# 7SEG_ClockLed.net
KiCad netlist of a schematic drawn in Altium Designer
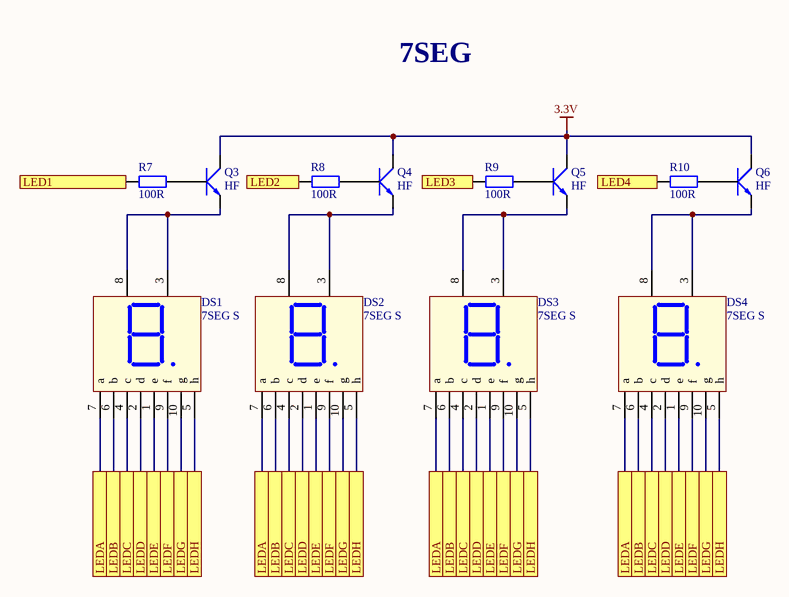
[diagram p0: 7SEG_ClockLed.SchDoc]

(export (version "E")
  (design (tool "Eeschema 10.0.6"))
  (components
    (comp (ref "DS1")
      (value "7SEG S")
      (footprint "7SEGS")
      (description "Single 7 Seg Dipslay")
      (libsource (lib "syhaunguyen") (part "LED7S"))
    )
    (comp (ref "DS2")
      (value "7SEG S")
      (footprint "7SEGS")
      (description "Single 7 Seg Dipslay")
      (libsource (lib "syhaunguyen") (part "LED7S"))
    )
    (comp (ref "DS3")
      (value "7SEG S")
      (footprint "7SEGS")
      (description "Single 7 Seg Dipslay")
      (libsource (lib "syhaunguyen") (part "LED7S"))
    )
    (comp (ref "DS4")
      (value "7SEG S")
      (footprint "7SEGS")
      (description "Single 7 Seg Dipslay")
      (libsource (lib "syhaunguyen") (part "LED7S"))
    )
    (comp (ref "Q3")
      (value "HF")
      (footprint "SOT23")
      (description "NPN transistor")
      (libsource (lib "Altium_Lib_by_KhueNguyenCreator") (part "C1815 HF SMD"))
    )
    (comp (ref "Q4")
      (value "HF")
      (footprint "SOT23")
      (description "NPN transistor")
      (libsource (lib "Altium_Lib_by_KhueNguyenCreator") (part "C1815 HF SMD"))
    )
    (comp (ref "Q5")
      (value "HF")
      (footprint "SOT23")
      (description "NPN transistor")
      (libsource (lib "Altium_Lib_by_KhueNguyenCreator") (part "C1815 HF SMD"))
    )
    (comp (ref "Q6")
      (value "HF")
      (footprint "SOT23")
      (description "NPN transistor")
      (libsource (lib "Altium_Lib_by_KhueNguyenCreator") (part "C1815 HF SMD"))
    )
    (comp (ref "R7")
      (value "100R")
      (footprint "tro smd 0805")
      (description "Dán")
      (libsource (lib "Altium_Lib_by_KhueNguyenCreator") (part "Tro 0805 5% 100R"))
    )
    (comp (ref "R8")
      (value "100R")
      (footprint "tro smd 0805")
      (description "Dán")
      (libsource (lib "Altium_Lib_by_KhueNguyenCreator") (part "Tro 0805 5% 100R"))
    )
    (comp (ref "R9")
      (value "100R")
      (footprint "tro smd 0805")
      (description "Dán")
      (libsource (lib "Altium_Lib_by_KhueNguyenCreator") (part "Tro 0805 5% 100R"))
    )
    (comp (ref "R10")
      (value "100R")
      (footprint "tro smd 0805")
      (description "Dán")
      (libsource (lib "Altium_Lib_by_KhueNguyenCreator") (part "Tro 0805 5% 100R"))
    )
  )
  (nets
    (net (code "1") (name "/LED1") (class "Default")
      (node (ref "R7") (pin "1") (pinfunction "1_1") (pintype "passive"))
    )
    (net (code "2") (name "/LED2") (class "Default")
      (node (ref "R8") (pin "1") (pinfunction "1_1") (pintype "passive"))
    )
    (net (code "3") (name "/LED3") (class "Default")
      (node (ref "R9") (pin "1") (pinfunction "1_1") (pintype "passive"))
    )
    (net (code "4") (name "/LED4") (class "Default")
      (node (ref "R10") (pin "1") (pinfunction "1_1") (pintype "passive"))
    )
    (net (code "5") (name "/LEDA") (class "Default")
      (node (ref "DS1") (pin "7") (pinfunction "a_7") (pintype "passive"))
      (node (ref "DS2") (pin "7") (pinfunction "a_7") (pintype "passive"))
      (node (ref "DS3") (pin "7") (pinfunction "a_7") (pintype "passive"))
      (node (ref "DS4") (pin "7") (pinfunction "a_7") (pintype "passive"))
    )
    (net (code "6") (name "/LEDB") (class "Default")
      (node (ref "DS1") (pin "6") (pinfunction "b_6") (pintype "passive"))
      (node (ref "DS2") (pin "6") (pinfunction "b_6") (pintype "passive"))
      (node (ref "DS3") (pin "6") (pinfunction "b_6") (pintype "passive"))
      (node (ref "DS4") (pin "6") (pinfunction "b_6") (pintype "passive"))
    )
    (net (code "7") (name "/LEDC") (class "Default")
      (node (ref "DS1") (pin "4") (pinfunction "c_4") (pintype "passive"))
      (node (ref "DS2") (pin "4") (pinfunction "c_4") (pintype "passive"))
      (node (ref "DS3") (pin "4") (pinfunction "c_4") (pintype "passive"))
      (node (ref "DS4") (pin "4") (pinfunction "c_4") (pintype "passive"))
    )
    (net (code "8") (name "/LEDD") (class "Default")
      (node (ref "DS1") (pin "2") (pinfunction "d_2") (pintype "passive"))
      (node (ref "DS2") (pin "2") (pinfunction "d_2") (pintype "passive"))
      (node (ref "DS3") (pin "2") (pinfunction "d_2") (pintype "passive"))
      (node (ref "DS4") (pin "2") (pinfunction "d_2") (pintype "passive"))
    )
    (net (code "9") (name "/LEDE") (class "Default")
      (node (ref "DS1") (pin "1") (pinfunction "e_1") (pintype "passive"))
      (node (ref "DS2") (pin "1") (pinfunction "e_1") (pintype "passive"))
      (node (ref "DS3") (pin "1") (pinfunction "e_1") (pintype "passive"))
      (node (ref "DS4") (pin "1") (pinfunction "e_1") (pintype "passive"))
    )
    (net (code "10") (name "/LEDF") (class "Default")
      (node (ref "DS1") (pin "9") (pinfunction "f_9") (pintype "passive"))
      (node (ref "DS2") (pin "9") (pinfunction "f_9") (pintype "passive"))
      (node (ref "DS3") (pin "9") (pinfunction "f_9") (pintype "passive"))
      (node (ref "DS4") (pin "9") (pinfunction "f_9") (pintype "passive"))
    )
    (net (code "11") (name "/LEDG") (class "Default")
      (node (ref "DS1") (pin "10") (pinfunction "g_10") (pintype "passive"))
      (node (ref "DS2") (pin "10") (pinfunction "g_10") (pintype "passive"))
      (node (ref "DS3") (pin "10") (pinfunction "g_10") (pintype "passive"))
      (node (ref "DS4") (pin "10") (pinfunction "g_10") (pintype "passive"))
    )
    (net (code "12") (name "/LEDH") (class "Default")
      (node (ref "DS1") (pin "5") (pinfunction "h_5") (pintype "passive"))
      (node (ref "DS2") (pin "5") (pinfunction "h_5") (pintype "passive"))
      (node (ref "DS3") (pin "5") (pinfunction "h_5") (pintype "passive"))
      (node (ref "DS4") (pin "5") (pinfunction "h_5") (pintype "passive"))
    )
    (net (code "13") (name "3.3V") (class "Default")
      (node (ref "Q3") (pin "3") (pinfunction "C_3") (pintype "passive"))
      (node (ref "Q4") (pin "3") (pinfunction "C_3") (pintype "passive"))
      (node (ref "Q5") (pin "3") (pinfunction "C_3") (pintype "passive"))
      (node (ref "Q6") (pin "3") (pinfunction "C_3") (pintype "passive"))
    )
    (net (code "14") (name "Net-(Q3-B)") (class "Default")
      (node (ref "Q3") (pin "1") (pinfunction "B_1") (pintype "passive"))
      (node (ref "R7") (pin "2") (pinfunction "2_2") (pintype "passive"))
    )
    (net (code "15") (name "Net-(Q3-E)") (class "Default")
      (node (ref "DS1") (pin "3") (pinfunction "Vcc_3") (pintype "passive"))
      (node (ref "DS1") (pin "8") (pinfunction "Vcc_8") (pintype "passive"))
      (node (ref "Q3") (pin "2") (pinfunction "E_2") (pintype "passive"))
    )
    (net (code "16") (name "Net-(Q4-B)") (class "Default")
      (node (ref "Q4") (pin "1") (pinfunction "B_1") (pintype "passive"))
      (node (ref "R8") (pin "2") (pinfunction "2_2") (pintype "passive"))
    )
    (net (code "17") (name "Net-(Q4-E)") (class "Default")
      (node (ref "DS2") (pin "3") (pinfunction "Vcc_3") (pintype "passive"))
      (node (ref "DS2") (pin "8") (pinfunction "Vcc_8") (pintype "passive"))
      (node (ref "Q4") (pin "2") (pinfunction "E_2") (pintype "passive"))
    )
    (net (code "18") (name "Net-(Q5-B)") (class "Default")
      (node (ref "Q5") (pin "1") (pinfunction "B_1") (pintype "passive"))
      (node (ref "R9") (pin "2") (pinfunction "2_2") (pintype "passive"))
    )
    (net (code "19") (name "Net-(Q5-E)") (class "Default")
      (node (ref "DS3") (pin "3") (pinfunction "Vcc_3") (pintype "passive"))
      (node (ref "DS3") (pin "8") (pinfunction "Vcc_8") (pintype "passive"))
      (node (ref "Q5") (pin "2") (pinfunction "E_2") (pintype "passive"))
    )
    (net (code "20") (name "Net-(Q6-B)") (class "Default")
      (node (ref "Q6") (pin "1") (pinfunction "B_1") (pintype "passive"))
      (node (ref "R10") (pin "2") (pinfunction "2_2") (pintype "passive"))
    )
    (net (code "21") (name "Net-(Q6-E)") (class "Default")
      (node (ref "DS4") (pin "3") (pinfunction "Vcc_3") (pintype "passive"))
      (node (ref "DS4") (pin "8") (pinfunction "Vcc_8") (pintype "passive"))
      (node (ref "Q6") (pin "2") (pinfunction "E_2") (pintype "passive"))
    )
  )
)
